# Sim_Sheet.net
KiCad netlist of a schematic drawn in Altium Designer
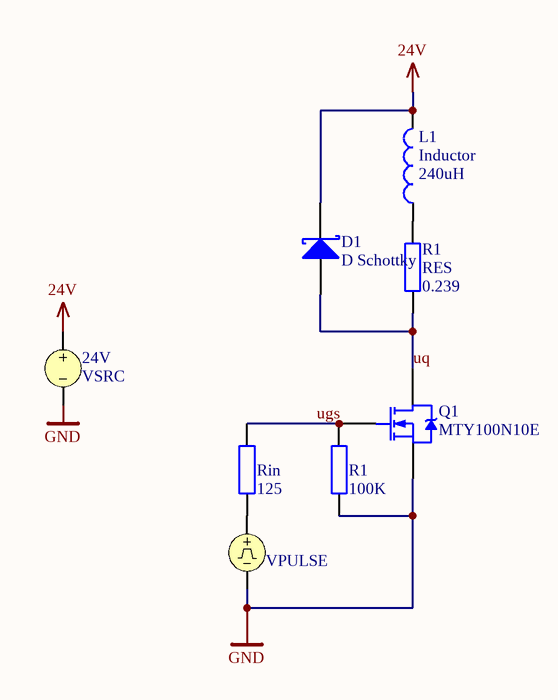
[diagram p0: Sim_Sheet.SchDoc]

(export (version "E")
  (design (tool "Eeschema 10.0.6"))
  (components
    (comp (ref "24V")
      (value "VSRC")
      (description "Voltage Source")
      (fields (field (name "PUBLISHER") "Altium Limited"))
      (libsource (lib "Simulation Sources") (part "VSRC"))
    )
    (comp (ref "D1")
      (value "D Schottky")
      (footprint "SMB")
      (description "Schottky Diode")
      (fields (field (name "PUBLISHER") "Altium Limited"))
      (libsource (lib "Miscellaneous Devices") (part "D Schottky"))
    )
    (comp (ref "L1")
      (value "Inductor")
      (footprint "0402-A")
      (fields (field (name "ALTIUM_VALUE") "240uH") (field (name "PUBLISHER") "Altium Limited"))
      (libsource (lib "Miscellaneous Devices") (part "Inductor"))
    )
    (comp (ref "Q1")
      (value "MTY100N10E")
      (footprint "Sode-part:TO-220V")
      (description "TMOS E-FET Power Field Effect Transistor")
      (fields (field (name "PUBLISHER") "Altium Limited"))
      (libsource (lib "Motorola Discrete MOSFET") (part "MTY100N10E"))
    )
    (comp (ref "R1")
      (value "RES")
      (footprint "Axial-0.4")
      (description "Widerstand")
      (fields (field (name "ALTIUM_VALUE") "0.239"))
      (libsource (lib "Sode-Sym") (part "RES"))
    )
    (comp (ref "R2")
      (value "R1")
      (footprint "Axial-0.4")
      (description "Widerstand")
      (fields (field (name "ALTIUM_VALUE") "100K"))
      (libsource (lib "Sode-Sym") (part "RES"))
    )
    (comp (ref "RIN1")
      (value "Rin")
      (footprint "Axial-0.4")
      (description "Widerstand")
      (fields (field (name "ALTIUM_VALUE") "125"))
      (libsource (lib "HTL-sym-2018-09") (part "RES"))
    )
    (comp (ref "µC")
      (value "VPULSE")
      (description "Pulse Voltage Source")
      (fields (field (name "PUBLISHER") "Altium Limited"))
      (libsource (lib "Simulation Sources") (part "VPULSE"))
    )
  )
  (nets
    (net (code "1") (name "/ugs") (class "Default")
      (node (ref "Q1") (pin "1") (pinfunction "G_1") (pintype "passive"))
      (node (ref "R2") (pin "1") (pintype "passive"))
      (node (ref "RIN1") (pin "2") (pintype "passive"))
    )
    (net (code "2") (name "/uq") (class "Default")
      (node (ref "D1") (pin "1") (pinfunction "A_1") (pintype "passive"))
      (node (ref "Q1") (pin "2") (pinfunction "D_2") (pintype "passive"))
      (node (ref "R1") (pin "1") (pintype "passive"))
    )
    (net (code "3") (name "24V") (class "Default")
      (node (ref "24V") (pin "1") (pinfunction "1_1") (pintype "passive"))
      (node (ref "D1") (pin "2") (pinfunction "K_2") (pintype "passive"))
      (node (ref "L1") (pin "2") (pinfunction "2_2") (pintype "passive"))
    )
    (net (code "4") (name "GND") (class "Default")
      (node (ref "Q1") (pin "3") (pinfunction "S_3") (pintype "passive"))
      (node (ref "R2") (pin "2") (pintype "passive"))
      (node (ref "µC") (pin "2") (pinfunction "2_2") (pintype "passive"))
    )
    (net (code "5") (name "Net-(L1-Pad1)") (class "Default")
      (node (ref "L1") (pin "1") (pinfunction "1_1") (pintype "passive"))
      (node (ref "R1") (pin "2") (pintype "passive"))
    )
    (net (code "6") (name "Net-(RIN1-Pad1)") (class "Default")
      (node (ref "RIN1") (pin "1") (pintype "passive"))
      (node (ref "µC") (pin "1") (pinfunction "1_1") (pintype "passive"))
    )
    (net (code "7") (name "unconnected-(24V-Pad2)") (class "Default")
      (node (ref "24V") (pin "2") (pinfunction "2_2") (pintype "passive"))
    )
  )
)
